# usb-hub-v0_5.net
KiCad netlist of a schematic drawn in EAGLE
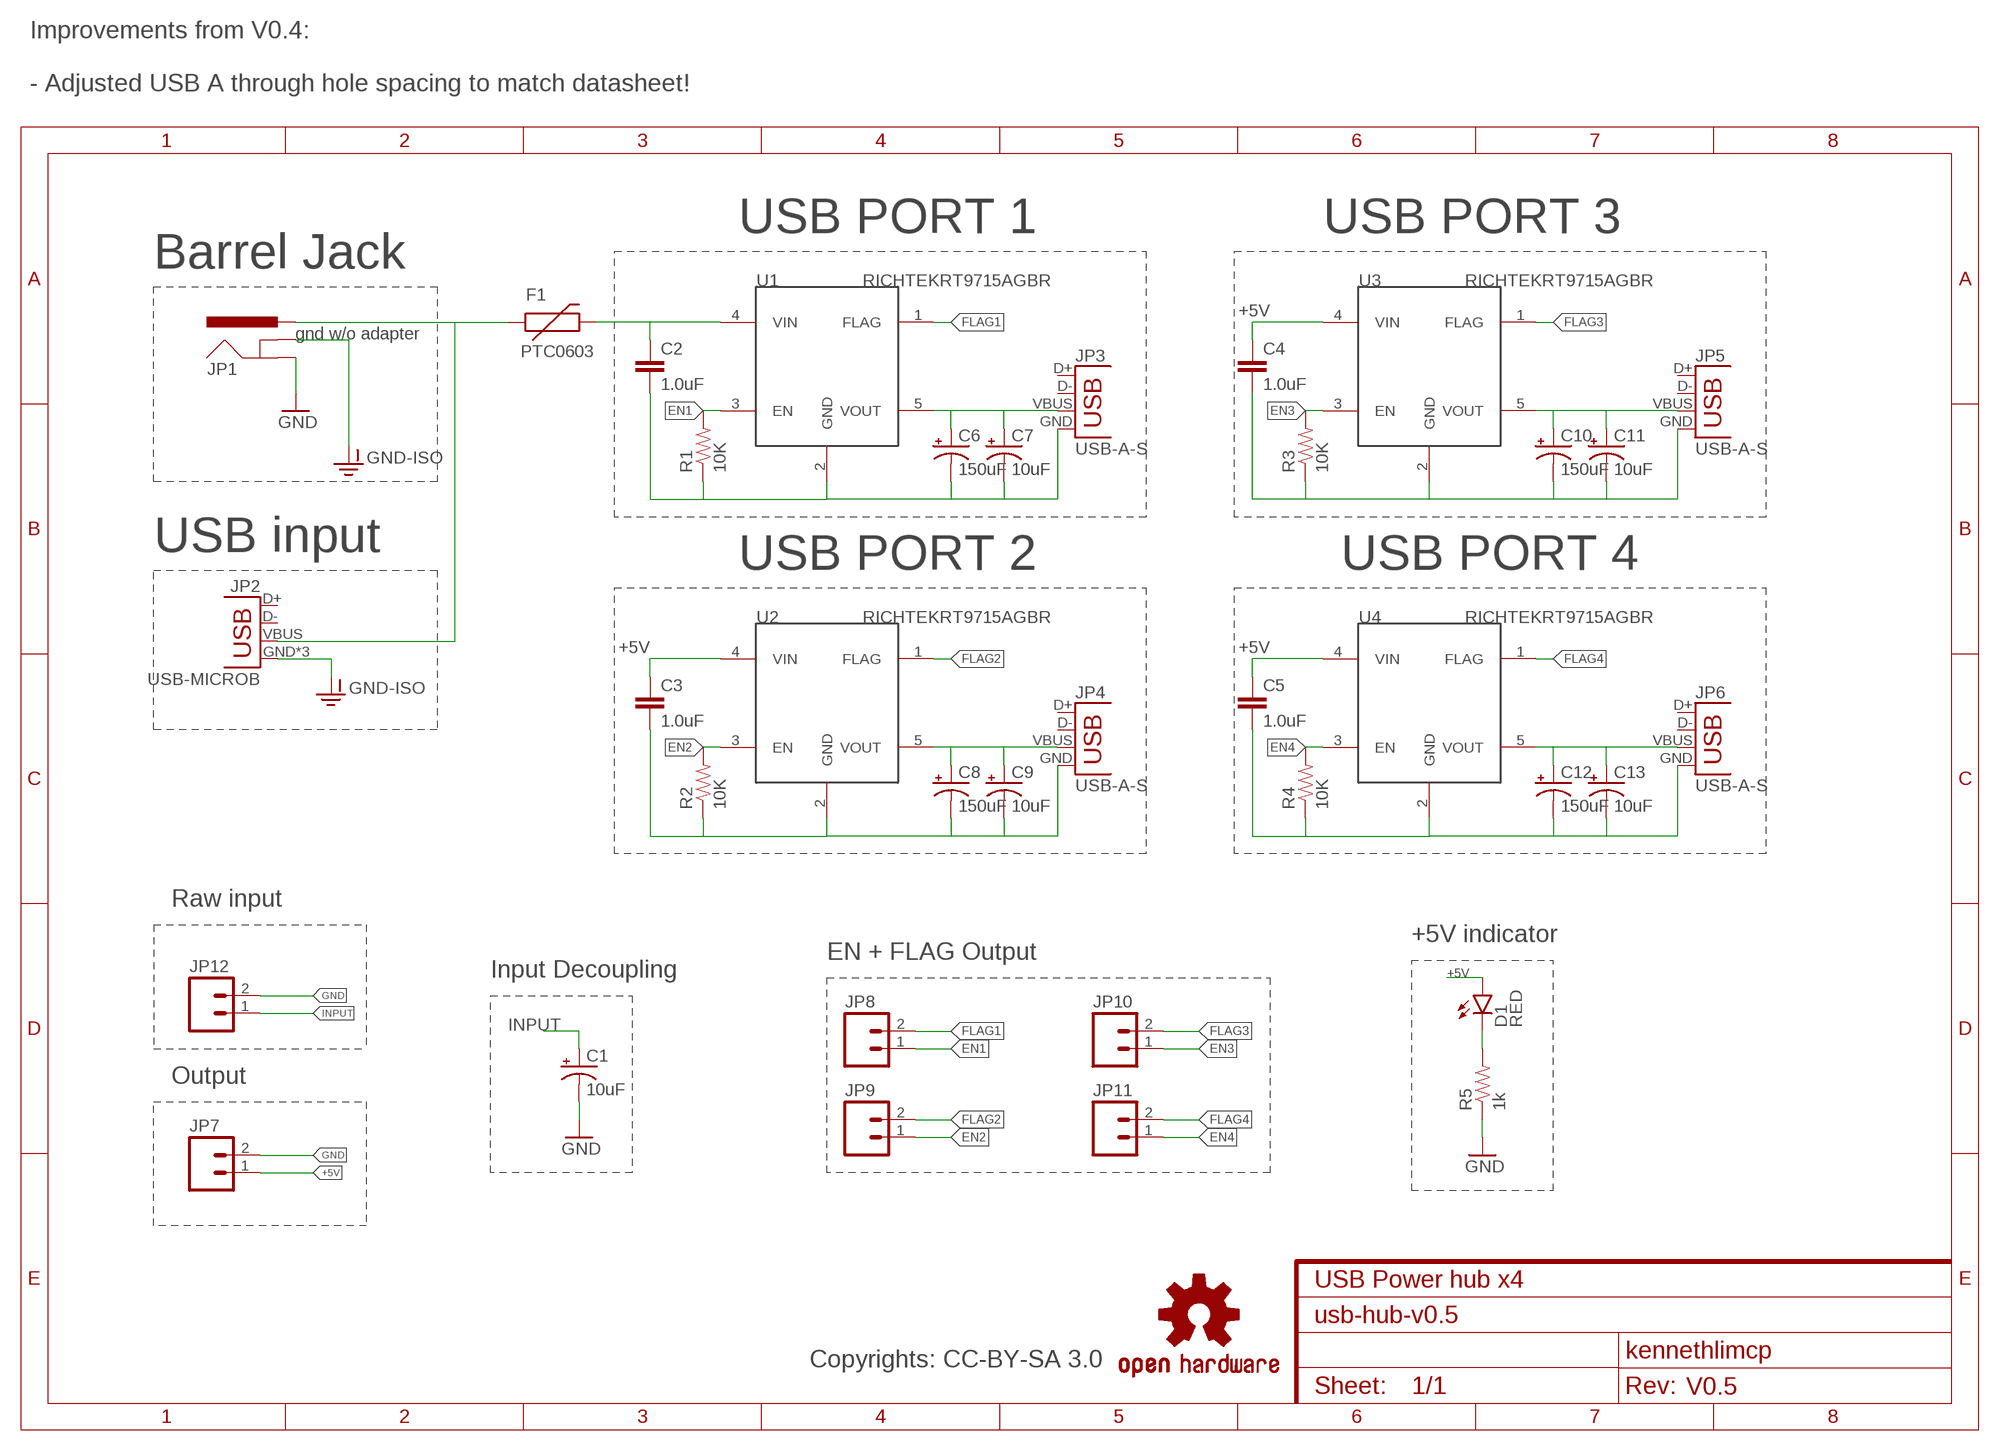
[diagram p0: schematic, sheet 1]

(export (version "E")
  (design (tool "Eeschema 10.0.6"))
  (components
    (comp (ref "C1")
      (value "10uF")
      (footprint "eagle-import:EIA3216")
      (libsource (lib "eagle-import") (part "10UF-16V-10%(TANT)"))
    )
    (comp (ref "C2")
      (value "1.0uF")
      (footprint "eagle-import:0603-CAP")
      (libsource (lib "eagle-import") (part "1.0UF-16V-10%(0603)"))
    )
    (comp (ref "C3")
      (value "1.0uF")
      (footprint "eagle-import:0603-CAP")
      (libsource (lib "eagle-import") (part "1.0UF-16V-10%(0603)"))
    )
    (comp (ref "C4")
      (value "1.0uF")
      (footprint "eagle-import:0603-CAP")
      (libsource (lib "eagle-import") (part "1.0UF-16V-10%(0603)"))
    )
    (comp (ref "C5")
      (value "1.0uF")
      (footprint "eagle-import:0603-CAP")
      (libsource (lib "eagle-import") (part "1.0UF-16V-10%(0603)"))
    )
    (comp (ref "C6")
      (value "150uF")
      (footprint "eagle-import:PANASONIC_D")
      (libsource (lib "eagle-import") (part "CAP_POLD"))
    )
    (comp (ref "C7")
      (value "10uF")
      (footprint "eagle-import:EIA3216")
      (libsource (lib "eagle-import") (part "10UF-16V-10%(TANT)"))
    )
    (comp (ref "C8")
      (value "150uF")
      (footprint "eagle-import:PANASONIC_D")
      (libsource (lib "eagle-import") (part "CAP_POLD"))
    )
    (comp (ref "C9")
      (value "10uF")
      (footprint "eagle-import:EIA3216")
      (libsource (lib "eagle-import") (part "10UF-16V-10%(TANT)"))
    )
    (comp (ref "C10")
      (value "150uF")
      (footprint "eagle-import:PANASONIC_D")
      (libsource (lib "eagle-import") (part "CAP_POLD"))
    )
    (comp (ref "C11")
      (value "10uF")
      (footprint "eagle-import:EIA3216")
      (libsource (lib "eagle-import") (part "10UF-16V-10%(TANT)"))
    )
    (comp (ref "C12")
      (value "150uF")
      (footprint "eagle-import:PANASONIC_D")
      (libsource (lib "eagle-import") (part "CAP_POLD"))
    )
    (comp (ref "C13")
      (value "10uF")
      (footprint "eagle-import:EIA3216")
      (libsource (lib "eagle-import") (part "10UF-16V-10%(TANT)"))
    )
    (comp (ref "D1")
      (value "RED")
      (footprint "eagle-import:LED-0603")
      (libsource (lib "eagle-import") (part "LED-RED0603"))
    )
    (comp (ref "F1")
      (value "PTC0603")
      (footprint "eagle-import:0603")
      (libsource (lib "eagle-import") (part "PTC0603"))
    )
    (comp (ref "JP1")
      (value "POWER_JACKPTH_LOCK")
      (footprint "eagle-import:POWER_JACK_PTH_LOCK")
      (libsource (lib "eagle-import") (part "POWER_JACKPTH_LOCK"))
    )
    (comp (ref "JP2")
      (value "USB-MICROB")
      (footprint "eagle-import:USB-MICROB")
      (libsource (lib "eagle-import") (part "USB-MICROB"))
    )
    (comp (ref "JP3")
      (value "USB-A-S")
      (footprint "eagle-import:USB-A-S")
      (libsource (lib "eagle-import") (part "USB-A-S"))
    )
    (comp (ref "JP4")
      (value "USB-A-S")
      (footprint "eagle-import:USB-A-S")
      (libsource (lib "eagle-import") (part "USB-A-S"))
    )
    (comp (ref "JP5")
      (value "USB-A-S")
      (footprint "eagle-import:USB-A-S")
      (libsource (lib "eagle-import") (part "USB-A-S"))
    )
    (comp (ref "JP6")
      (value "USB-A-S")
      (footprint "eagle-import:USB-A-S")
      (libsource (lib "eagle-import") (part "USB-A-S"))
    )
    (comp (ref "JP7")
      (value "M02PTH")
      (footprint "eagle-import:1X02")
      (libsource (lib "eagle-import") (part "M02PTH"))
    )
    (comp (ref "JP8")
      (value "M02PTH")
      (footprint "eagle-import:1X02")
      (libsource (lib "eagle-import") (part "M02PTH"))
    )
    (comp (ref "JP9")
      (value "M02PTH")
      (footprint "eagle-import:1X02")
      (libsource (lib "eagle-import") (part "M02PTH"))
    )
    (comp (ref "JP10")
      (value "M02PTH")
      (footprint "eagle-import:1X02")
      (libsource (lib "eagle-import") (part "M02PTH"))
    )
    (comp (ref "JP11")
      (value "M02PTH")
      (footprint "eagle-import:1X02")
      (libsource (lib "eagle-import") (part "M02PTH"))
    )
    (comp (ref "JP12")
      (value "M02PTH")
      (footprint "eagle-import:1X02")
      (libsource (lib "eagle-import") (part "M02PTH"))
    )
    (comp (ref "LOGO1")
      (value "OSHW-LOGOPAD")
      (footprint "eagle-import:OSHW-LOGO-M-PAD")
      (libsource (lib "eagle-import") (part "OSHW-LOGOPAD"))
    )
    (comp (ref "R1")
      (value "10K")
      (footprint "eagle-import:0402-RES")
      (libsource (lib "eagle-import") (part "RESISTOR0402"))
    )
    (comp (ref "R2")
      (value "10K")
      (footprint "eagle-import:0402-RES")
      (libsource (lib "eagle-import") (part "RESISTOR0402"))
    )
    (comp (ref "R3")
      (value "10K")
      (footprint "eagle-import:0402-RES")
      (libsource (lib "eagle-import") (part "RESISTOR0402"))
    )
    (comp (ref "R4")
      (value "10K")
      (footprint "eagle-import:0402-RES")
      (libsource (lib "eagle-import") (part "RESISTOR0402"))
    )
    (comp (ref "R5")
      (value "1k")
      (footprint "eagle-import:0402-RES")
      (libsource (lib "eagle-import") (part "RESISTOR0402"))
    )
    (comp (ref "U1")
      (value "RICHTEKRT9715AGBR")
      (footprint "eagle-import:SOT23-5")
      (libsource (lib "eagle-import") (part "RICHTEKRT9715AGBR"))
    )
    (comp (ref "U2")
      (value "RICHTEKRT9715AGBR")
      (footprint "eagle-import:SOT23-5")
      (libsource (lib "eagle-import") (part "RICHTEKRT9715AGBR"))
    )
    (comp (ref "U3")
      (value "RICHTEKRT9715AGBR")
      (footprint "eagle-import:SOT23-5")
      (libsource (lib "eagle-import") (part "RICHTEKRT9715AGBR"))
    )
    (comp (ref "U4")
      (value "RICHTEKRT9715AGBR")
      (footprint "eagle-import:SOT23-5")
      (libsource (lib "eagle-import") (part "RICHTEKRT9715AGBR"))
    )
  )
  (nets
    (net (code "1") (name "+5V") (class "Default")
      (node (ref "C2") (pin "1") (pinfunction "1_1") (pintype "passive"))
      (node (ref "C3") (pin "1") (pinfunction "1_1") (pintype "passive"))
      (node (ref "C4") (pin "1") (pinfunction "1_1") (pintype "passive"))
      (node (ref "C5") (pin "1") (pinfunction "1_1") (pintype "passive"))
      (node (ref "D1") (pin "A") (pinfunction "A_A") (pintype "passive"))
      (node (ref "F1") (pin "2") (pinfunction "2_2") (pintype "bidirectional"))
      (node (ref "JP7") (pin "1") (pinfunction "1_1") (pintype "passive"))
      (node (ref "U1") (pin "4") (pinfunction "VIN_4") (pintype "bidirectional"))
      (node (ref "U2") (pin "4") (pinfunction "VIN_4") (pintype "bidirectional"))
      (node (ref "U3") (pin "4") (pinfunction "VIN_4") (pintype "bidirectional"))
      (node (ref "U4") (pin "4") (pinfunction "VIN_4") (pintype "bidirectional"))
    )
    (net (code "2") (name "EN1") (class "Default")
      (node (ref "JP8") (pin "1") (pinfunction "1_1") (pintype "passive"))
      (node (ref "R1") (pin "2") (pinfunction "2_2") (pintype "passive"))
      (node (ref "U1") (pin "3") (pinfunction "EN_3") (pintype "bidirectional"))
    )
    (net (code "3") (name "EN2") (class "Default")
      (node (ref "JP9") (pin "1") (pinfunction "1_1") (pintype "passive"))
      (node (ref "R2") (pin "2") (pinfunction "2_2") (pintype "passive"))
      (node (ref "U2") (pin "3") (pinfunction "EN_3") (pintype "bidirectional"))
    )
    (net (code "4") (name "EN3") (class "Default")
      (node (ref "JP10") (pin "1") (pinfunction "1_1") (pintype "passive"))
      (node (ref "R3") (pin "2") (pinfunction "2_2") (pintype "passive"))
      (node (ref "U3") (pin "3") (pinfunction "EN_3") (pintype "bidirectional"))
    )
    (net (code "5") (name "EN4") (class "Default")
      (node (ref "JP11") (pin "1") (pinfunction "1_1") (pintype "passive"))
      (node (ref "R4") (pin "2") (pinfunction "2_2") (pintype "passive"))
      (node (ref "U4") (pin "3") (pinfunction "EN_3") (pintype "bidirectional"))
    )
    (net (code "6") (name "FLAG1") (class "Default")
      (node (ref "JP8") (pin "2") (pinfunction "2_2") (pintype "passive"))
      (node (ref "U1") (pin "1") (pinfunction "FLAG_1") (pintype "bidirectional"))
    )
    (net (code "7") (name "FLAG2") (class "Default")
      (node (ref "JP9") (pin "2") (pinfunction "2_2") (pintype "passive"))
      (node (ref "U2") (pin "1") (pinfunction "FLAG_1") (pintype "bidirectional"))
    )
    (net (code "8") (name "FLAG3") (class "Default")
      (node (ref "JP10") (pin "2") (pinfunction "2_2") (pintype "passive"))
      (node (ref "U3") (pin "1") (pinfunction "FLAG_1") (pintype "bidirectional"))
    )
    (net (code "9") (name "FLAG4") (class "Default")
      (node (ref "JP11") (pin "2") (pinfunction "2_2") (pintype "passive"))
      (node (ref "U4") (pin "1") (pinfunction "FLAG_1") (pintype "bidirectional"))
    )
    (net (code "10") (name "GND") (class "Default")
      (node (ref "C1") (pin "C") (pinfunction "-_C") (pintype "passive"))
      (node (ref "C10") (pin "-") (pinfunction "-_-") (pintype "passive"))
      (node (ref "C11") (pin "C") (pinfunction "-_C") (pintype "passive"))
      (node (ref "C12") (pin "-") (pinfunction "-_-") (pintype "passive"))
      (node (ref "C13") (pin "C") (pinfunction "-_C") (pintype "passive"))
      (node (ref "C2") (pin "2") (pinfunction "2_2") (pintype "passive"))
      (node (ref "C3") (pin "2") (pinfunction "2_2") (pintype "passive"))
      (node (ref "C4") (pin "2") (pinfunction "2_2") (pintype "passive"))
      (node (ref "C5") (pin "2") (pinfunction "2_2") (pintype "passive"))
      (node (ref "C6") (pin "-") (pinfunction "-_-") (pintype "passive"))
      (node (ref "C7") (pin "C") (pinfunction "-_C") (pintype "passive"))
      (node (ref "C8") (pin "-") (pinfunction "-_-") (pintype "passive"))
      (node (ref "C9") (pin "C") (pinfunction "-_C") (pintype "passive"))
      (node (ref "JP1") (pin "GND") (pinfunction "GND_GND") (pintype "bidirectional"))
      (node (ref "JP12") (pin "2") (pinfunction "2_2") (pintype "passive"))
      (node (ref "JP3") (pin "GND") (pinfunction "GND_GND") (pintype "bidirectional"))
      (node (ref "JP4") (pin "GND") (pinfunction "GND_GND") (pintype "bidirectional"))
      (node (ref "JP5") (pin "GND") (pinfunction "GND_GND") (pintype "bidirectional"))
      (node (ref "JP6") (pin "GND") (pinfunction "GND_GND") (pintype "bidirectional"))
      (node (ref "JP7") (pin "2") (pinfunction "2_2") (pintype "passive"))
      (node (ref "R1") (pin "1") (pinfunction "1_1") (pintype "passive"))
      (node (ref "R2") (pin "1") (pinfunction "1_1") (pintype "passive"))
      (node (ref "R3") (pin "1") (pinfunction "1_1") (pintype "passive"))
      (node (ref "R4") (pin "1") (pinfunction "1_1") (pintype "passive"))
      (node (ref "R5") (pin "1") (pinfunction "1_1") (pintype "passive"))
      (node (ref "U1") (pin "2") (pinfunction "GND_2") (pintype "bidirectional"))
      (node (ref "U2") (pin "2") (pinfunction "GND_2") (pintype "bidirectional"))
      (node (ref "U3") (pin "2") (pinfunction "GND_2") (pintype "bidirectional"))
      (node (ref "U4") (pin "2") (pinfunction "GND_2") (pintype "bidirectional"))
    )
    (net (code "11") (name "GND-ISO") (class "Default")
      (node (ref "JP1") (pin "GNDBREAK") (pinfunction "GNDBREAK_GNDBREAK") (pintype "bidirectional"))
      (node (ref "JP2") (pin "GND") (pinfunction "GND_GND") (pintype "bidirectional"))
      (node (ref "JP2") (pin "MT1") (pinfunction "GND_MT1") (pintype "bidirectional"))
      (node (ref "JP2") (pin "MT2") (pinfunction "GND_MT2") (pintype "bidirectional"))
    )
    (net (code "12") (name "INPUT") (class "Default")
      (node (ref "C1") (pin "A") (pinfunction "+_A") (pintype "passive"))
      (node (ref "F1") (pin "1") (pinfunction "1_1") (pintype "bidirectional"))
      (node (ref "JP1") (pin "PWR") (pinfunction "PWR_PWR") (pintype "bidirectional"))
      (node (ref "JP12") (pin "1") (pinfunction "1_1") (pintype "passive"))
      (node (ref "JP2") (pin "VBUS") (pinfunction "VBUS_VBUS") (pintype "bidirectional"))
    )
    (net (code "13") (name "Net-(C7-+)") (class "Default")
      (node (ref "C6") (pin "+") (pinfunction "+_+") (pintype "passive"))
      (node (ref "C7") (pin "A") (pinfunction "+_A") (pintype "passive"))
      (node (ref "JP3") (pin "VBUS") (pinfunction "VBUS_VBUS") (pintype "bidirectional"))
      (node (ref "U1") (pin "5") (pinfunction "VOUT_5") (pintype "bidirectional"))
    )
    (net (code "14") (name "Net-(C9-+)") (class "Default")
      (node (ref "C8") (pin "+") (pinfunction "+_+") (pintype "passive"))
      (node (ref "C9") (pin "A") (pinfunction "+_A") (pintype "passive"))
      (node (ref "JP4") (pin "VBUS") (pinfunction "VBUS_VBUS") (pintype "bidirectional"))
      (node (ref "U2") (pin "5") (pinfunction "VOUT_5") (pintype "bidirectional"))
    )
    (net (code "15") (name "Net-(C11-+)") (class "Default")
      (node (ref "C10") (pin "+") (pinfunction "+_+") (pintype "passive"))
      (node (ref "C11") (pin "A") (pinfunction "+_A") (pintype "passive"))
      (node (ref "JP5") (pin "VBUS") (pinfunction "VBUS_VBUS") (pintype "bidirectional"))
      (node (ref "U3") (pin "5") (pinfunction "VOUT_5") (pintype "bidirectional"))
    )
    (net (code "16") (name "Net-(C13-+)") (class "Default")
      (node (ref "C12") (pin "+") (pinfunction "+_+") (pintype "passive"))
      (node (ref "C13") (pin "A") (pinfunction "+_A") (pintype "passive"))
      (node (ref "JP6") (pin "VBUS") (pinfunction "VBUS_VBUS") (pintype "bidirectional"))
      (node (ref "U4") (pin "5") (pinfunction "VOUT_5") (pintype "bidirectional"))
    )
    (net (code "17") (name "Net-(D1-PadC)") (class "Default")
      (node (ref "D1") (pin "C") (pinfunction "C_C") (pintype "passive"))
      (node (ref "R5") (pin "2") (pinfunction "2_2") (pintype "passive"))
    )
    (net (code "18") (name "unconnected-(JP2-PadD+)") (class "Default")
      (node (ref "JP2") (pin "D+") (pinfunction "D+_D+") (pintype "bidirectional"))
    )
    (net (code "19") (name "unconnected-(JP2-PadD-)") (class "Default")
      (node (ref "JP2") (pin "D-") (pinfunction "D-_D-") (pintype "bidirectional"))
    )
    (net (code "20") (name "unconnected-(JP3-PadD+)") (class "Default")
      (node (ref "JP3") (pin "D+") (pinfunction "D+_D+") (pintype "bidirectional"))
    )
    (net (code "21") (name "unconnected-(JP3-PadD-)") (class "Default")
      (node (ref "JP3") (pin "D-") (pinfunction "D-_D-") (pintype "bidirectional"))
    )
    (net (code "22") (name "unconnected-(JP4-PadD+)") (class "Default")
      (node (ref "JP4") (pin "D+") (pinfunction "D+_D+") (pintype "bidirectional"))
    )
    (net (code "23") (name "unconnected-(JP4-PadD-)") (class "Default")
      (node (ref "JP4") (pin "D-") (pinfunction "D-_D-") (pintype "bidirectional"))
    )
    (net (code "24") (name "unconnected-(JP5-PadD+)") (class "Default")
      (node (ref "JP5") (pin "D+") (pinfunction "D+_D+") (pintype "bidirectional"))
    )
    (net (code "25") (name "unconnected-(JP5-PadD-)") (class "Default")
      (node (ref "JP5") (pin "D-") (pinfunction "D-_D-") (pintype "bidirectional"))
    )
    (net (code "26") (name "unconnected-(JP6-PadD+)") (class "Default")
      (node (ref "JP6") (pin "D+") (pinfunction "D+_D+") (pintype "bidirectional"))
    )
    (net (code "27") (name "unconnected-(JP6-PadD-)") (class "Default")
      (node (ref "JP6") (pin "D-") (pinfunction "D-_D-") (pintype "bidirectional"))
    )
  )
)
